# V1_7.net
KiCad netlist of a schematic drawn in Altium Designer
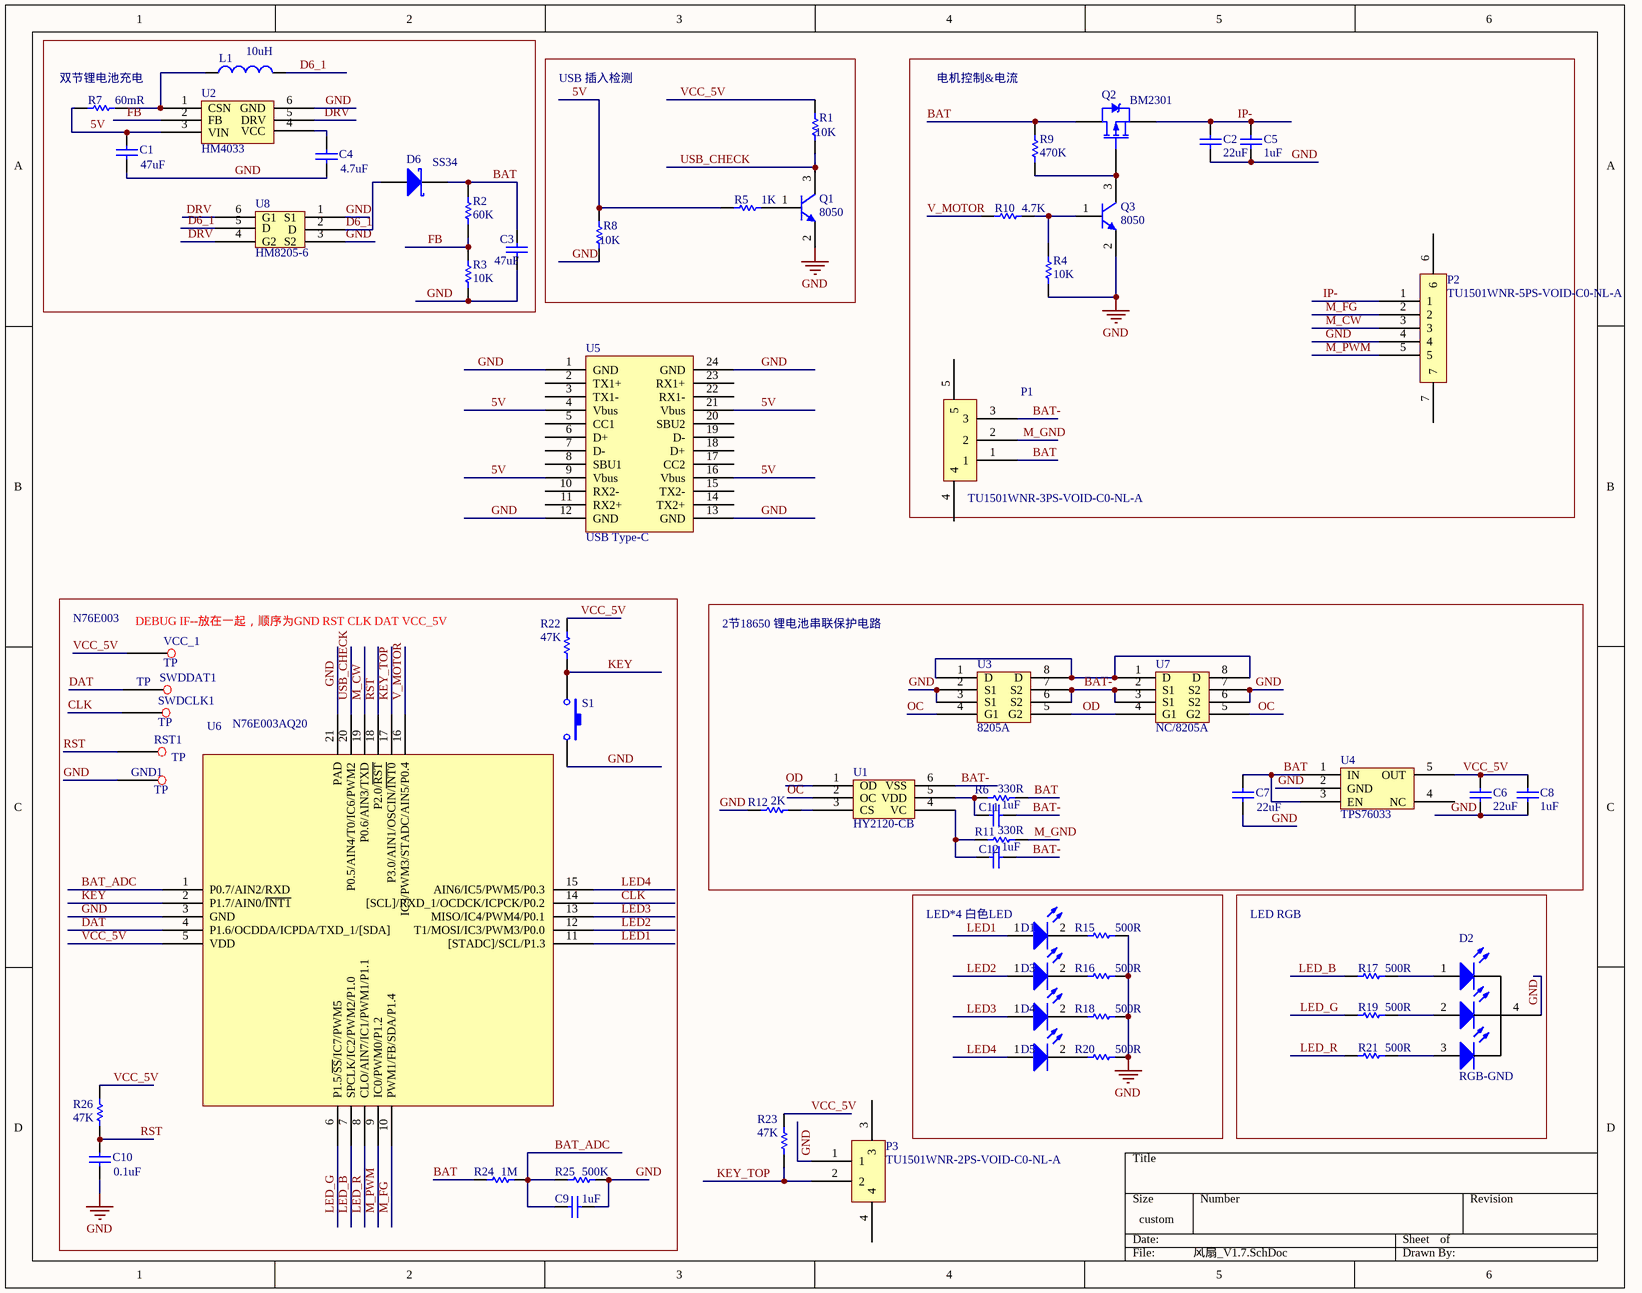
[diagram p0: 风扇_V1.7.SchDoc]

(export (version "E")
  (design (tool "Eeschema 10.0.6"))
  (components
    (comp (ref "C1")
      (value "47uF")
      (footprint "C-0603")
      (description "Capacitor")
      (fields (field (name "PUBLISHER") "Altium Limited"))
      (libsource (lib "Miscellaneous Devices") (part "Cap"))
    )
    (comp (ref "C2")
      (value "22uF")
      (footprint "C-0603")
      (description "Capacitor")
      (fields (field (name "PUBLISHER") "Altium Limited"))
      (libsource (lib "Miscellaneous Devices") (part "Cap"))
    )
    (comp (ref "C3")
      (value "47uF")
      (footprint "C-0603")
      (description "Capacitor")
      (fields (field (name "PUBLISHER") "Altium Limited"))
      (libsource (lib "Miscellaneous Devices") (part "Cap"))
    )
    (comp (ref "C4")
      (value "4.7uF")
      (footprint "C-0402")
      (description "Capacitor")
      (fields (field (name "PUBLISHER") "Altium Limited"))
      (libsource (lib "Miscellaneous Devices") (part "Cap"))
    )
    (comp (ref "C5")
      (value "1uF")
      (footprint "C-0402")
      (description "Capacitor")
      (fields (field (name "PUBLISHER") "Altium Limited"))
      (libsource (lib "Miscellaneous Devices") (part "Cap"))
    )
    (comp (ref "C6")
      (value "22uF")
      (footprint "C-0603")
      (description "Capacitor")
      (fields (field (name "PUBLISHER") "Altium Limited"))
      (libsource (lib "Miscellaneous Devices") (part "Cap"))
    )
    (comp (ref "C7")
      (value "22uF")
      (footprint "C-0603")
      (description "Capacitor")
      (fields (field (name "PUBLISHER") "Altium Limited"))
      (libsource (lib "Miscellaneous Devices") (part "Cap"))
    )
    (comp (ref "C8")
      (value "1uF")
      (footprint "C-0402")
      (description "Capacitor")
      (fields (field (name "PUBLISHER") "Altium Limited"))
      (libsource (lib "Miscellaneous Devices") (part "Cap"))
    )
    (comp (ref "C9")
      (value "1uF")
      (footprint "C-0402")
      (description "Capacitor")
      (fields (field (name "PUBLISHER") "Altium Limited"))
      (libsource (lib "Miscellaneous Devices") (part "Cap"))
    )
    (comp (ref "C10")
      (value "0.1uF")
      (footprint "C-0402")
      (description "Capacitor")
      (fields (field (name "PUBLISHER") "Altium Limited"))
      (libsource (lib "Miscellaneous Devices") (part "Cap"))
    )
    (comp (ref "C11")
      (value "1uF")
      (footprint "C-0402")
      (description "Capacitor")
      (fields (field (name "PUBLISHER") "Altium Limited"))
      (libsource (lib "Miscellaneous Devices") (part "Cap"))
    )
    (comp (ref "C12")
      (value "1uF")
      (footprint "C-0402")
      (description "Capacitor")
      (fields (field (name "PUBLISHER") "Altium Limited"))
      (libsource (lib "Miscellaneous Devices") (part "Cap"))
    )
    (comp (ref "D1")
      (value "LED0")
      (footprint "LED-0603")
      (description "Typical INFRARED GaAs LED")
      (fields (field (name "PUBLISHER") "Altium Limited"))
      (libsource (lib "Miscellaneous Devices") (part "LED0"))
    )
    (comp (ref "D2")
      (value "RGB-GND")
      (footprint "0603*2-LED")
      (libsource (lib "Others_IC_SCH_LIB") (part "RGB-GND"))
    )
    (comp (ref "D3")
      (value "LED0")
      (footprint "LED-0603")
      (description "Typical INFRARED GaAs LED")
      (fields (field (name "PUBLISHER") "Altium Limited"))
      (libsource (lib "Miscellaneous Devices") (part "LED0"))
    )
    (comp (ref "D4")
      (value "LED0")
      (footprint "LED-0603")
      (description "Typical INFRARED GaAs LED")
      (fields (field (name "PUBLISHER") "Altium Limited"))
      (libsource (lib "Miscellaneous Devices") (part "LED0"))
    )
    (comp (ref "D5")
      (value "LED0")
      (footprint "LED-0603")
      (description "Typical INFRARED GaAs LED")
      (fields (field (name "PUBLISHER") "Altium Limited"))
      (libsource (lib "Miscellaneous Devices") (part "LED0"))
    )
    (comp (ref "D6")
      (value "SS34")
      (footprint "HM4033 V1.0:DSMD")
      (description "Schottky Rectifier")
      (fields (field (name "PUBLISHER") "Altium Limited"))
      (libsource (lib "Miscellaneous Devices") (part "Diode 10TQ035"))
    )
    (comp (ref "GND1") (value "TP") (footprint "TP-1.5") (libsource (lib "Others_IC_SCH_LIB") (part "TP")))
    (comp (ref "L1")
      (value "10uH")
      (footprint "L-SMD")
      (description "Inductor")
      (fields (field (name "PUBLISHER") "Altium Limited"))
      (libsource (lib "Miscellaneous Devices") (part "Inductor"))
    )
    (comp (ref "P1")
      (value "TU1501WNR-3PS-VOID-C0-NL-A")
      (footprint "TU1501WNR-3PS-VOID-*-NL-A")
      (libsource (lib "Others_IC_SCH_LIB") (part "TU1501WNR-3PS-VOID-C0-NL-A"))
    )
    (comp (ref "P2")
      (value "TU1501WNR-5PS-VOID-C0-NL-A")
      (footprint "TU1501WNR-5PS-VOID-*-NL-A")
      (libsource (lib "Others_IC_SCH_LIB") (part "TU1501WNR-5PS-VOID-C0-NL-A"))
    )
    (comp (ref "P3")
      (value "TU1501WNR-2PS-VOID-C0-NL-A")
      (footprint "TU1501WNR-2PS-VOID-*-NL-A")
      (libsource (lib "Others_IC_SCH_LIB") (part "TU1501WNR-2PS-VOID-C0-NL-A"))
    )
    (comp (ref "Q1")
      (value "8050")
      (footprint "SOT-23")
      (description "NPN Bipolar Transistor")
      (fields (field (name "PUBLISHER") "Altium Limited"))
      (libsource (lib "Miscellaneous Devices") (part "NPN"))
    )
    (comp (ref "Q2")
      (value "BM2301")
      (footprint "SOT-23")
      (description "P-Channel Power MOSFET")
      (fields (field (name "PUBLISHER") "Altium Limited"))
      (libsource (lib "Miscellaneous Devices") (part "PMOS-2"))
    )
    (comp (ref "Q3")
      (value "8050")
      (footprint "SOT-23")
      (description "NPN Bipolar Transistor")
      (fields (field (name "PUBLISHER") "Altium Limited"))
      (libsource (lib "Miscellaneous Devices") (part "NPN"))
    )
    (comp (ref "R1")
      (value "10K")
      (footprint "R-0402")
      (description "Resistor")
      (fields (field (name "PUBLISHER") "Altium Limited"))
      (libsource (lib "Miscellaneous Devices") (part "Res1"))
    )
    (comp (ref "R2")
      (value "60K")
      (footprint "R-0402")
      (description "Resistor")
      (fields (field (name "PUBLISHER") "Altium Limited"))
      (libsource (lib "Miscellaneous Devices") (part "Res1"))
    )
    (comp (ref "R3")
      (value "10K")
      (footprint "R-0402")
      (description "Resistor")
      (fields (field (name "PUBLISHER") "Altium Limited"))
      (libsource (lib "Miscellaneous Devices") (part "Res1"))
    )
    (comp (ref "R4")
      (value "10K")
      (footprint "R-0402")
      (description "Resistor")
      (fields (field (name "PUBLISHER") "Altium Limited"))
      (libsource (lib "Miscellaneous Devices") (part "Res1"))
    )
    (comp (ref "R5")
      (value "1K")
      (footprint "R-0402")
      (description "Resistor")
      (fields (field (name "PUBLISHER") "Altium Limited"))
      (libsource (lib "Miscellaneous Devices") (part "Res1"))
    )
    (comp (ref "R6")
      (value "330R")
      (footprint "R-0402")
      (description "Resistor")
      (fields (field (name "PUBLISHER") "Altium Limited"))
      (libsource (lib "Miscellaneous Devices") (part "Res1"))
    )
    (comp (ref "R7")
      (value "60mR")
      (footprint "R-0402")
      (description "Resistor")
      (fields (field (name "PUBLISHER") "Altium Limited"))
      (libsource (lib "Miscellaneous Devices") (part "Res1"))
    )
    (comp (ref "R8")
      (value "10K")
      (footprint "R-0402")
      (description "Resistor")
      (fields (field (name "PUBLISHER") "Altium Limited"))
      (libsource (lib "Miscellaneous Devices") (part "Res1"))
    )
    (comp (ref "R9")
      (value "470K")
      (footprint "R-0402")
      (description "Resistor")
      (fields (field (name "PUBLISHER") "Altium Limited"))
      (libsource (lib "Miscellaneous Devices") (part "Res1"))
    )
    (comp (ref "R10")
      (value "4.7K")
      (footprint "R-0402")
      (description "Resistor")
      (fields (field (name "PUBLISHER") "Altium Limited"))
      (libsource (lib "Miscellaneous Devices") (part "Res1"))
    )
    (comp (ref "R11")
      (value "330R")
      (footprint "R-0402")
      (description "Resistor")
      (fields (field (name "PUBLISHER") "Altium Limited"))
      (libsource (lib "Miscellaneous Devices") (part "Res1"))
    )
    (comp (ref "R12")
      (value "2K")
      (footprint "R-0402")
      (description "Resistor")
      (fields (field (name "PUBLISHER") "Altium Limited"))
      (libsource (lib "Miscellaneous Devices") (part "Res1"))
    )
    (comp (ref "R15")
      (value "500R")
      (footprint "R-0402")
      (description "Resistor")
      (fields (field (name "PUBLISHER") "Altium Limited"))
      (libsource (lib "Miscellaneous Devices") (part "Res1"))
    )
    (comp (ref "R16")
      (value "500R")
      (footprint "R-0402")
      (description "Resistor")
      (fields (field (name "PUBLISHER") "Altium Limited"))
      (libsource (lib "Miscellaneous Devices") (part "Res1"))
    )
    (comp (ref "R17")
      (value "500R")
      (footprint "R-0402")
      (description "Resistor")
      (fields (field (name "PUBLISHER") "Altium Limited"))
      (libsource (lib "Miscellaneous Devices") (part "Res1"))
    )
    (comp (ref "R18")
      (value "500R")
      (footprint "R-0402")
      (description "Resistor")
      (fields (field (name "PUBLISHER") "Altium Limited"))
      (libsource (lib "Miscellaneous Devices") (part "Res1"))
    )
    (comp (ref "R19")
      (value "500R")
      (footprint "R-0402")
      (description "Resistor")
      (fields (field (name "PUBLISHER") "Altium Limited"))
      (libsource (lib "Miscellaneous Devices") (part "Res1"))
    )
    (comp (ref "R20")
      (value "500R")
      (footprint "R-0402")
      (description "Resistor")
      (fields (field (name "PUBLISHER") "Altium Limited"))
      (libsource (lib "Miscellaneous Devices") (part "Res1"))
    )
    (comp (ref "R21")
      (value "500R")
      (footprint "R-0402")
      (description "Resistor")
      (fields (field (name "PUBLISHER") "Altium Limited"))
      (libsource (lib "Miscellaneous Devices") (part "Res1"))
    )
    (comp (ref "R22")
      (value "47K")
      (footprint "R-0402")
      (description "Resistor")
      (fields (field (name "PUBLISHER") "Altium Limited"))
      (libsource (lib "Miscellaneous Devices") (part "Res1"))
    )
    (comp (ref "R23")
      (value "47K")
      (footprint "R-0402")
      (description "Resistor")
      (fields (field (name "PUBLISHER") "Altium Limited"))
      (libsource (lib "Miscellaneous Devices") (part "Res1"))
    )
    (comp (ref "R24")
      (value "1M")
      (footprint "R-0402")
      (description "Resistor")
      (fields (field (name "PUBLISHER") "Altium Limited"))
      (libsource (lib "Miscellaneous Devices") (part "Res1"))
    )
    (comp (ref "R25")
      (value "500K")
      (footprint "R-0402")
      (description "Resistor")
      (fields (field (name "PUBLISHER") "Altium Limited"))
      (libsource (lib "Miscellaneous Devices") (part "Res1"))
    )
    (comp (ref "R26")
      (value "47K")
      (footprint "R-0402")
      (description "Resistor")
      (fields (field (name "PUBLISHER") "Altium Limited"))
      (libsource (lib "Miscellaneous Devices") (part "Res1"))
    )
    (comp (ref "RST1") (value "TP") (footprint "TP-1.5") (libsource (lib "Others_IC_SCH_LIB") (part "TP")))
    (comp (ref "S1")
      (value "SW-PB")
      (footprint "SWITCH-4P-SMT")
      (description "Switch")
      (fields (field (name "PUBLISHER") "Altium Limited"))
      (libsource (lib "Miscellaneous Devices") (part "SW-PB"))
    )
    (comp (ref "SWDCLK1") (value "TP") (footprint "TP-1.5") (libsource (lib "Others_IC_SCH_LIB") (part "TP")))
    (comp (ref "SWDDAT1") (value "TP") (footprint "TP-1.5") (libsource (lib "Others_IC_SCH_LIB") (part "TP")))
    (comp (ref "U1")
      (value "HY2120-CB")
      (footprint "SOT-23-6L")
      (libsource (lib "Others_IC_SCH_LIB") (part "HY2120"))
    )
    (comp (ref "U2")
      (value "HM4033")
      (footprint "SOT-23-6L")
      (libsource (lib "Others_IC_SCH_LIB") (part "HM4033"))
    )
    (comp (ref "U3")
      (value "8205A")
      (footprint "TSSOP8")
      (libsource (lib "Others_IC_SCH_LIB") (part "8205A"))
    )
    (comp (ref "U4")
      (value "TPS76033")
      (footprint "SOT-23-5")
      (libsource (lib "Others_IC_SCH_LIB") (part "TPS76033"))
    )
    (comp (ref "U5")
      (value "USB Type-C")
      (footprint "USB-type C")
      (libsource (lib "Others_IC_SCH_LIB") (part "USB Type-C"))
    )
    (comp (ref "U6")
      (value "N76E003AQ20")
      (footprint "QFN-20 0.4mm")
      (libsource (lib "Others_IC_SCH_LIB") (part "N76E003AQ20"))
    )
    (comp (ref "U7")
      (value "NC/8205A")
      (footprint "TSSOP8")
      (libsource (lib "Others_IC_SCH_LIB") (part "8205A"))
    )
    (comp (ref "U8")
      (value "HM8205-6")
      (footprint "SOT-23-6L")
      (libsource (lib "Others_IC_SCH_LIB") (part "HM8205-6"))
    )
    (comp (ref "VCC_1") (value "TP") (footprint "TP-1.5") (libsource (lib "Others_IC_SCH_LIB") (part "TP")))
  )
  (nets
    (net (code "1") (name "/5V") (class "Default")
      (node (ref "C1") (pin "1") (pinfunction "1_1") (pintype "passive"))
      (node (ref "R5") (pin "1") (pinfunction "1_1") (pintype "passive"))
      (node (ref "R7") (pin "2") (pinfunction "2_2") (pintype "passive"))
      (node (ref "R8") (pin "1") (pinfunction "1_1") (pintype "passive"))
      (node (ref "U2") (pin "3") (pinfunction "VIN_3") (pintype "passive"))
      (node (ref "U5") (pin "16") (pinfunction "Vbus_16") (pintype "passive"))
      (node (ref "U5") (pin "21") (pinfunction "Vbus_21") (pintype "passive"))
      (node (ref "U5") (pin "4") (pinfunction "Vbus_4") (pintype "passive"))
      (node (ref "U5") (pin "9") (pinfunction "Vbus_9") (pintype "passive"))
    )
    (net (code "2") (name "/BAT") (class "Default")
      (node (ref "C3") (pin "2") (pinfunction "2_2") (pintype "passive"))
      (node (ref "C7") (pin "2") (pinfunction "2_2") (pintype "passive"))
      (node (ref "D6") (pin "1") (pinfunction "K_1") (pintype "passive"))
      (node (ref "P1") (pin "1") (pinfunction "1_1") (pintype "passive"))
      (node (ref "Q2") (pin "2") (pinfunction "D_2") (pintype "passive"))
      (node (ref "R2") (pin "1") (pinfunction "1_1") (pintype "passive"))
      (node (ref "R24") (pin "1") (pinfunction "1_1") (pintype "passive"))
      (node (ref "R6") (pin "2") (pinfunction "2_2") (pintype "passive"))
      (node (ref "R9") (pin "2") (pinfunction "2_2") (pintype "passive"))
      (node (ref "U4") (pin "1") (pinfunction "IN_1") (pintype "passive"))
      (node (ref "U4") (pin "3") (pinfunction "EN_3") (pintype "passive"))
    )
    (net (code "3") (name "/BAT-") (class "Default")
      (node (ref "C11") (pin "1") (pinfunction "1_1") (pintype "passive"))
      (node (ref "C12") (pin "1") (pinfunction "1_1") (pintype "passive"))
      (node (ref "P1") (pin "3") (pinfunction "3_3") (pintype "passive"))
      (node (ref "U1") (pin "6") (pinfunction "VSS_6") (pintype "passive"))
      (node (ref "U3") (pin "6") (pinfunction "S2_6") (pintype "passive"))
      (node (ref "U3") (pin "7") (pinfunction "S2_7") (pintype "passive"))
      (node (ref "U7") (pin "2") (pinfunction "S1_2") (pintype "passive"))
      (node (ref "U7") (pin "3") (pinfunction "S1_3") (pintype "passive"))
    )
    (net (code "4") (name "/BAT_ADC") (class "Default")
      (node (ref "C9") (pin "2") (pinfunction "2_2") (pintype "passive"))
      (node (ref "R24") (pin "2") (pinfunction "2_2") (pintype "passive"))
      (node (ref "R25") (pin "1") (pinfunction "1_1") (pintype "passive"))
      (node (ref "U6") (pin "1") (pinfunction "P0.7/AIN2/RXD_1") (pintype "passive"))
    )
    (net (code "5") (name "/CLK") (class "Default")
      (node (ref "SWDCLK1") (pin "1") (pinfunction "1_1") (pintype "passive"))
      (node (ref "U6") (pin "14") (pinfunction "[SCL]/RXD_1/OCDCK/ICPCK/P0.2_14") (pintype "passive"))
    )
    (net (code "6") (name "/D6_1") (class "Default")
      (node (ref "D6") (pin "3") (pinfunction "A_3") (pintype "passive"))
      (node (ref "L1") (pin "2") (pinfunction "2_2") (pintype "passive"))
      (node (ref "U8") (pin "2") (pinfunction "D_2") (pintype "passive"))
      (node (ref "U8") (pin "5") (pinfunction "D_5") (pintype "passive"))
    )
    (net (code "7") (name "/DAT") (class "Default")
      (node (ref "SWDDAT1") (pin "1") (pinfunction "1_1") (pintype "passive"))
      (node (ref "U6") (pin "4") (pinfunction "P1.6/OCDDA/ICPDA/TXD_1/[SDA]_4") (pintype "passive"))
    )
    (net (code "8") (name "/DRV") (class "Default")
      (node (ref "U2") (pin "5") (pinfunction "DRV_5") (pintype "passive"))
      (node (ref "U8") (pin "4") (pinfunction "G2_4") (pintype "passive"))
      (node (ref "U8") (pin "6") (pinfunction "G1_6") (pintype "passive"))
    )
    (net (code "9") (name "/FB") (class "Default")
      (node (ref "R2") (pin "2") (pinfunction "2_2") (pintype "passive"))
      (node (ref "R3") (pin "1") (pinfunction "1_1") (pintype "passive"))
      (node (ref "U2") (pin "2") (pinfunction "FB_2") (pintype "passive"))
    )
    (net (code "10") (name "/IP-") (class "Default")
      (node (ref "C2") (pin "2") (pinfunction "2_2") (pintype "passive"))
      (node (ref "C5") (pin "2") (pinfunction "2_2") (pintype "passive"))
      (node (ref "P2") (pin "1") (pinfunction "1_1") (pintype "passive"))
      (node (ref "Q2") (pin "3") (pinfunction "S_3") (pintype "passive"))
    )
    (net (code "11") (name "/KEY") (class "Default")
      (node (ref "R22") (pin "1") (pinfunction "1_1") (pintype "passive"))
      (node (ref "S1") (pin "1") (pinfunction "1_1") (pintype "passive"))
      (node (ref "U6") (pin "2") (pinfunction "P1.7/AIN0/~{INT1}_2") (pintype "passive"))
    )
    (net (code "12") (name "/KEY_TOP") (class "Default")
      (node (ref "P3") (pin "2") (pinfunction "2_2") (pintype "passive"))
      (node (ref "R23") (pin "1") (pinfunction "1_1") (pintype "passive"))
      (node (ref "U6") (pin "17") (pinfunction "P3.0/AIN1/OSCIN/~{INT0}_17") (pintype "passive"))
    )
    (net (code "13") (name "/LED1") (class "Default")
      (node (ref "D1") (pin "1") (pinfunction "A_1") (pintype "passive"))
      (node (ref "U6") (pin "11") (pinfunction "[STADC]/SCL/P1.3_11") (pintype "passive"))
    )
    (net (code "14") (name "/LED2") (class "Default")
      (node (ref "D3") (pin "1") (pinfunction "A_1") (pintype "passive"))
      (node (ref "U6") (pin "12") (pinfunction "T1/MOSI/IC3/PWM3/P0.0_12") (pintype "passive"))
    )
    (net (code "15") (name "/LED3") (class "Default")
      (node (ref "D4") (pin "1") (pinfunction "A_1") (pintype "passive"))
      (node (ref "U6") (pin "13") (pinfunction "MISO/IC4/PWM4/P0.1_13") (pintype "passive"))
    )
    (net (code "16") (name "/LED4") (class "Default")
      (node (ref "D5") (pin "1") (pinfunction "A_1") (pintype "passive"))
      (node (ref "U6") (pin "15") (pinfunction "AIN6/IC5/PWM5/P0.3_15") (pintype "passive"))
    )
    (net (code "17") (name "/LED_B") (class "Default")
      (node (ref "R17") (pin "1") (pinfunction "1_1") (pintype "passive"))
      (node (ref "U6") (pin "7") (pinfunction "SPCLK/IC2/PWM2/P1.0_7") (pintype "passive"))
    )
    (net (code "18") (name "/LED_G") (class "Default")
      (node (ref "R19") (pin "1") (pinfunction "1_1") (pintype "passive"))
      (node (ref "U6") (pin "6") (pinfunction "P1.5/~{SS}/IC7/PWM5_6") (pintype "passive"))
    )
    (net (code "19") (name "/LED_R") (class "Default")
      (node (ref "R21") (pin "1") (pinfunction "1_1") (pintype "passive"))
      (node (ref "U6") (pin "8") (pinfunction "CLO/AIN7/IC1/PWM1/P1.1_8") (pintype "passive"))
    )
    (net (code "20") (name "/M_CW") (class "Default")
      (node (ref "P2") (pin "3") (pinfunction "3_3") (pintype "passive"))
      (node (ref "U6") (pin "19") (pinfunction "P0.6/AIN3/TXD_19") (pintype "passive"))
    )
    (net (code "21") (name "/M_FG") (class "Default")
      (node (ref "P2") (pin "2") (pinfunction "2_2") (pintype "passive"))
      (node (ref "U6") (pin "10") (pinfunction "PWM1/FB/SDA/P1.4_10") (pintype "passive"))
    )
    (net (code "22") (name "/M_GND") (class "Default")
      (node (ref "P1") (pin "2") (pinfunction "2_2") (pintype "passive"))
      (node (ref "R11") (pin "2") (pinfunction "2_2") (pintype "passive"))
    )
    (net (code "23") (name "/M_PWM") (class "Default")
      (node (ref "P2") (pin "5") (pinfunction "5_5") (pintype "passive"))
      (node (ref "U6") (pin "9") (pinfunction "IC0/PWM0/P1.2_9") (pintype "passive"))
    )
    (net (code "24") (name "/OC") (class "Default")
      (node (ref "U1") (pin "2") (pinfunction "OC_2") (pintype "passive"))
      (node (ref "U3") (pin "4") (pinfunction "G1_4") (pintype "passive"))
      (node (ref "U7") (pin "5") (pinfunction "G2_5") (pintype "passive"))
    )
    (net (code "25") (name "/OD") (class "Default")
      (node (ref "U1") (pin "1") (pinfunction "OD_1") (pintype "passive"))
      (node (ref "U3") (pin "5") (pinfunction "G2_5") (pintype "passive"))
      (node (ref "U7") (pin "4") (pinfunction "G1_4") (pintype "passive"))
    )
    (net (code "26") (name "/RST") (class "Default")
      (node (ref "C10") (pin "2") (pinfunction "2_2") (pintype "passive"))
      (node (ref "R26") (pin "1") (pinfunction "1_1") (pintype "passive"))
      (node (ref "RST1") (pin "1") (pinfunction "1_1") (pintype "passive"))
      (node (ref "U6") (pin "18") (pinfunction "P2.0/~{RST}_18") (pintype "passive"))
    )
    (net (code "27") (name "/USB_CHECK") (class "Default")
      (node (ref "Q1") (pin "3") (pinfunction "C_3") (pintype "passive"))
      (node (ref "R1") (pin "1") (pinfunction "1_1") (pintype "passive"))
      (node (ref "U6") (pin "20") (pinfunction "P0.5/AIN4/T0/IC6/PWM2_20") (pintype "passive"))
    )
    (net (code "28") (name "/VCC_5V") (class "Default")
      (node (ref "C6") (pin "2") (pinfunction "2_2") (pintype "passive"))
      (node (ref "C8") (pin "2") (pinfunction "2_2") (pintype "passive"))
      (node (ref "R1") (pin "2") (pinfunction "2_2") (pintype "passive"))
      (node (ref "R22") (pin "2") (pinfunction "2_2") (pintype "passive"))
      (node (ref "R23") (pin "2") (pinfunction "2_2") (pintype "passive"))
      (node (ref "R26") (pin "2") (pinfunction "2_2") (pintype "passive"))
      (node (ref "U4") (pin "5") (pinfunction "OUT_5") (pintype "passive"))
      (node (ref "U6") (pin "5") (pinfunction "VDD_5") (pintype "passive"))
      (node (ref "VCC_1") (pin "1") (pinfunction "1_1") (pintype "passive"))
    )
    (net (code "29") (name "/V_MOTOR") (class "Default")
      (node (ref "R10") (pin "1") (pinfunction "1_1") (pintype "passive"))
      (node (ref "U6") (pin "16") (pinfunction "IC3/PWM3/STADC/AIN5/P0.4_16") (pintype "passive"))
    )
    (net (code "30") (name "GND") (class "Default")
      (node (ref "C1") (pin "2") (pinfunction "2_2") (pintype "passive"))
      (node (ref "C10") (pin "1") (pinfunction "1_1") (pintype "passive"))
      (node (ref "C2") (pin "1") (pinfunction "1_1") (pintype "passive"))
      (node (ref "C3") (pin "1") (pinfunction "1_1") (pintype "passive"))
      (node (ref "C4") (pin "2") (pinfunction "2_2") (pintype "passive"))
      (node (ref "C5") (pin "1") (pinfunction "1_1") (pintype "passive"))
      (node (ref "C6") (pin "1") (pinfunction "1_1") (pintype "passive"))
      (node (ref "C7") (pin "1") (pinfunction "1_1") (pintype "passive"))
      (node (ref "C8") (pin "1") (pinfunction "1_1") (pintype "passive"))
      (node (ref "C9") (pin "1") (pinfunction "1_1") (pintype "passive"))
      (node (ref "D2") (pin "4") (pinfunction "4_4") (pintype "passive"))
      (node (ref "GND1") (pin "1") (pinfunction "1_1") (pintype "passive"))
      (node (ref "P2") (pin "4") (pinfunction "4_4") (pintype "passive"))
      (node (ref "P3") (pin "1") (pinfunction "1_1") (pintype "passive"))
      (node (ref "Q1") (pin "2") (pinfunction "E_2") (pintype "passive"))
      (node (ref "Q3") (pin "2") (pinfunction "E_2") (pintype "passive"))
      (node (ref "R12") (pin "1") (pinfunction "1_1") (pintype "passive"))
      (node (ref "R15") (pin "2") (pinfunction "2_2") (pintype "passive"))
      (node (ref "R16") (pin "2") (pinfunction "2_2") (pintype "passive"))
      (node (ref "R18") (pin "2") (pinfunction "2_2") (pintype "passive"))
      (node (ref "R20") (pin "2") (pinfunction "2_2") (pintype "passive"))
      (node (ref "R25") (pin "2") (pinfunction "2_2") (pintype "passive"))
      (node (ref "R3") (pin "2") (pinfunction "2_2") (pintype "passive"))
      (node (ref "R4") (pin "1") (pinfunction "1_1") (pintype "passive"))
      (node (ref "R8") (pin "2") (pinfunction "2_2") (pintype "passive"))
      (node (ref "S1") (pin "2") (pinfunction "2_2") (pintype "passive"))
      (node (ref "U2") (pin "6") (pinfunction "GND_6") (pintype "passive"))
      (node (ref "U3") (pin "2") (pinfunction "S1_2") (pintype "passive"))
      (node (ref "U3") (pin "3") (pinfunction "S1_3") (pintype "passive"))
      (node (ref "U4") (pin "2") (pinfunction "GND_2") (pintype "passive"))
      (node (ref "U5") (pin "1") (pinfunction "GND_1") (pintype "passive"))
      (node (ref "U5") (pin "12") (pinfunction "GND_12") (pintype "passive"))
      (node (ref "U5") (pin "13") (pinfunction "GND_13") (pintype "passive"))
      (node (ref "U5") (pin "24") (pinfunction "GND_24") (pintype "passive"))
      (node (ref "U6") (pin "21") (pinfunction "PAD_21") (pintype "passive"))
      (node (ref "U6") (pin "3") (pinfunction "GND_3") (pintype "passive"))
      (node (ref "U7") (pin "6") (pinfunction "S2_6") (pintype "passive"))
      (node (ref "U7") (pin "7") (pinfunction "S2_7") (pintype "passive"))
      (node (ref "U8") (pin "1") (pinfunction "S1_1") (pintype "passive"))
      (node (ref "U8") (pin "3") (pinfunction "S2_3") (pintype "passive"))
    )
    (net (code "31") (name "Net-(D1-K)") (class "Default")
      (node (ref "D1") (pin "2") (pinfunction "K_2") (pintype "passive"))
      (node (ref "R15") (pin "1") (pinfunction "1_1") (pintype "passive"))
    )
    (net (code "32") (name "Net-(D2-Pad1)") (class "Default")
      (node (ref "D2") (pin "1") (pinfunction "1_1") (pintype "passive"))
      (node (ref "R17") (pin "2") (pinfunction "2_2") (pintype "passive"))
    )
    (net (code "33") (name "Net-(D2-Pad2)") (class "Default")
      (node (ref "D2") (pin "2") (pinfunction "2_2") (pintype "passive"))
      (node (ref "R19") (pin "2") (pinfunction "2_2") (pintype "passive"))
    )
    (net (code "34") (name "Net-(D2-Pad3)") (class "Default")
      (node (ref "D2") (pin "3") (pinfunction "3_3") (pintype "passive"))
      (node (ref "R21") (pin "2") (pinfunction "2_2") (pintype "passive"))
    )
    (net (code "35") (name "Net-(D3-K)") (class "Default")
      (node (ref "D3") (pin "2") (pinfunction "K_2") (pintype "passive"))
      (node (ref "R16") (pin "1") (pinfunction "1_1") (pintype "passive"))
    )
    (net (code "36") (name "Net-(D4-K)") (class "Default")
      (node (ref "D4") (pin "2") (pinfunction "K_2") (pintype "passive"))
      (node (ref "R18") (pin "1") (pinfunction "1_1") (pintype "passive"))
    )
    (net (code "37") (name "Net-(D5-K)") (class "Default")
      (node (ref "D5") (pin "2") (pinfunction "K_2") (pintype "passive"))
      (node (ref "R20") (pin "1") (pinfunction "1_1") (pintype "passive"))
    )
    (net (code "38") (name "Net-(Q1-B)") (class "Default")
      (node (ref "Q1") (pin "1") (pinfunction "B_1") (pintype "passive"))
      (node (ref "R5") (pin "2") (pinfunction "2_2") (pintype "passive"))
    )
    (net (code "39") (name "Net-(Q2-G)") (class "Default")
      (node (ref "Q2") (pin "1") (pinfunction "G_1") (pintype "passive"))
      (node (ref "Q3") (pin "3") (pinfunction "C_3") (pintype "passive"))
      (node (ref "R9") (pin "1") (pinfunction "1_1") (pintype "passive"))
    )
    (net (code "40") (name "Net-(Q3-B)") (class "Default")
      (node (ref "Q3") (pin "1") (pinfunction "B_1") (pintype "passive"))
      (node (ref "R10") (pin "2") (pinfunction "2_2") (pintype "passive"))
      (node (ref "R4") (pin "2") (pinfunction "2_2") (pintype "passive"))
    )
    (net (code "41") (name "Net-(U1-CS)") (class "Default")
      (node (ref "R12") (pin "2") (pinfunction "2_2") (pintype "passive"))
      (node (ref "U1") (pin "3") (pinfunction "CS_3") (pintype "passive"))
    )
    (net (code "42") (name "Net-(U1-VC)") (class "Default")
      (node (ref "C12") (pin "2") (pinfunction "2_2") (pintype "passive"))
      (node (ref "R11") (pin "1") (pinfunction "1_1") (pintype "passive"))
      (node (ref "U1") (pin "4") (pinfunction "VC_4") (pintype "passive"))
    )
    (net (code "43") (name "Net-(U1-VDD)") (class "Default")
      (node (ref "C11") (pin "2") (pinfunction "2_2") (pintype "passive"))
      (node (ref "R6") (pin "1") (pinfunction "1_1") (pintype "passive"))
      (node (ref "U1") (pin "5") (pinfunction "VDD_5") (pintype "passive"))
    )
    (net (code "44") (name "Net-(U2-CSN)") (class "Default")
      (node (ref "L1") (pin "1") (pinfunction "1_1") (pintype "passive"))
      (node (ref "R7") (pin "1") (pinfunction "1_1") (pintype "passive"))
      (node (ref "U2") (pin "1") (pinfunction "CSN_1") (pintype "passive"))
    )
    (net (code "45") (name "Net-(U2-VCC)") (class "Default")
      (node (ref "C4") (pin "1") (pinfunction "1_1") (pintype "passive"))
      (node (ref "U2") (pin "4") (pinfunction "VCC_4") (pintype "passive"))
    )
    (net (code "46") (name "Net-(U3-D-Pad1)") (class "Default")
      (node (ref "U3") (pin "1") (pinfunction "D_1") (pintype "passive"))
      (node (ref "U3") (pin "8") (pinfunction "D_8") (pintype "passive"))
      (node (ref "U7") (pin "1") (pinfunction "D_1") (pintype "passive"))
      (node (ref "U7") (pin "8") (pinfunction "D_8") (pintype "passive"))
    )
    (net (code "47") (name "unconnected-(P1-Pad4)") (class "Default")
      (node (ref "P1") (pin "4") (pinfunction "4_4") (pintype "passive"))
    )
    (net (code "48") (name "unconnected-(P1-Pad5)") (class "Default")
      (node (ref "P1") (pin "5") (pinfunction "5_5") (pintype "passive"))
    )
    (net (code "49") (name "unconnected-(P2-Pad6)") (class "Default")
      (node (ref "P2") (pin "6") (pinfunction "6_6") (pintype "passive"))
    )
    (net (code "50") (name "unconnected-(P2-Pad7)") (class "Default")
      (node (ref "P2") (pin "7") (pinfunction "7_7") (pintype "passive"))
    )
    (net (code "51") (name "unconnected-(P3-Pad3)") (class "Default")
      (node (ref "P3") (pin "3") (pinfunction "3_3") (pintype "passive"))
    )
    (net (code "52") (name "unconnected-(P3-Pad4)") (class "Default")
      (node (ref "P3") (pin "4") (pinfunction "4_4") (pintype "passive"))
    )
    (net (code "53") (name "unconnected-(U4-NC-Pad4)") (class "Default")
      (node (ref "U4") (pin "4") (pinfunction "NC_4") (pintype "passive"))
    )
    (net (code "54") (name "unconnected-(U5-CC1-Pad5)") (class "Default")
      (node (ref "U5") (pin "5") (pinfunction "CC1_5") (pintype "passive"))
    )
    (net (code "55") (name "unconnected-(U5-CC2-Pad17)") (class "Default")
      (node (ref "U5") (pin "17") (pinfunction "CC2_17") (pintype "passive"))
    )
    (net (code "56") (name "unconnected-(U5-D+-Pad6)") (class "Default")
      (node (ref "U5") (pin "6") (pinfunction "D+_6") (pintype "passive"))
    )
    (net (code "57") (name "unconnected-(U5-D+-Pad18)") (class "Default")
      (node (ref "U5") (pin "18") (pinfunction "D+_18") (pintype "passive"))
    )
    (net (code "58") (name "unconnected-(U5-D--Pad7)") (class "Default")
      (node (ref "U5") (pin "7") (pinfunction "D-_7") (pintype "passive"))
    )
    (net (code "59") (name "unconnected-(U5-D--Pad19)") (class "Default")
      (node (ref "U5") (pin "19") (pinfunction "D-_19") (pintype "passive"))
    )
    (net (code "60") (name "unconnected-(U5-RX1+-Pad23)") (class "Default")
      (node (ref "U5") (pin "23") (pinfunction "RX1+_23") (pintype "passive"))
    )
    (net (code "61") (name "unconnected-(U5-RX1--Pad22)") (class "Default")
      (node (ref "U5") (pin "22") (pinfunction "RX1-_22") (pintype "passive"))
    )
    (net (code "62") (name "unconnected-(U5-RX2+-Pad11)") (class "Default")
      (node (ref "U5") (pin "11") (pinfunction "RX2+_11") (pintype "passive"))
    )
    (net (code "63") (name "unconnected-(U5-RX2--Pad10)") (class "Default")
      (node (ref "U5") (pin "10") (pinfunction "RX2-_10") (pintype "passive"))
    )
    (net (code "64") (name "unconnected-(U5-SBU1-Pad8)") (class "Default")
      (node (ref "U5") (pin "8") (pinfunction "SBU1_8") (pintype "passive"))
    )
    (net (code "65") (name "unconnected-(U5-SBU2-Pad20)") (class "Default")
      (node (ref "U5") (pin "20") (pinfunction "SBU2_20") (pintype "passive"))
    )
    (net (code "66") (name "unconnected-(U5-TX1+-Pad2)") (class "Default")
      (node (ref "U5") (pin "2") (pinfunction "TX1+_2") (pintype "passive"))
    )
    (net (code "67") (name "unconnected-(U5-TX1--Pad3)") (class "Default")
      (node (ref "U5") (pin "3") (pinfunction "TX1-_3") (pintype "passive"))
    )
    (net (code "68") (name "unconnected-(U5-TX2+-Pad14)") (class "Default")
      (node (ref "U5") (pin "14") (pinfunction "TX2+_14") (pintype "passive"))
    )
    (net (code "69") (name "unconnected-(U5-TX2--Pad15)") (class "Default")
      (node (ref "U5") (pin "15") (pinfunction "TX2-_15") (pintype "passive"))
    )
  )
)
